# Dual_Servo_Module.net
KiCad netlist of a schematic drawn in EAGLE
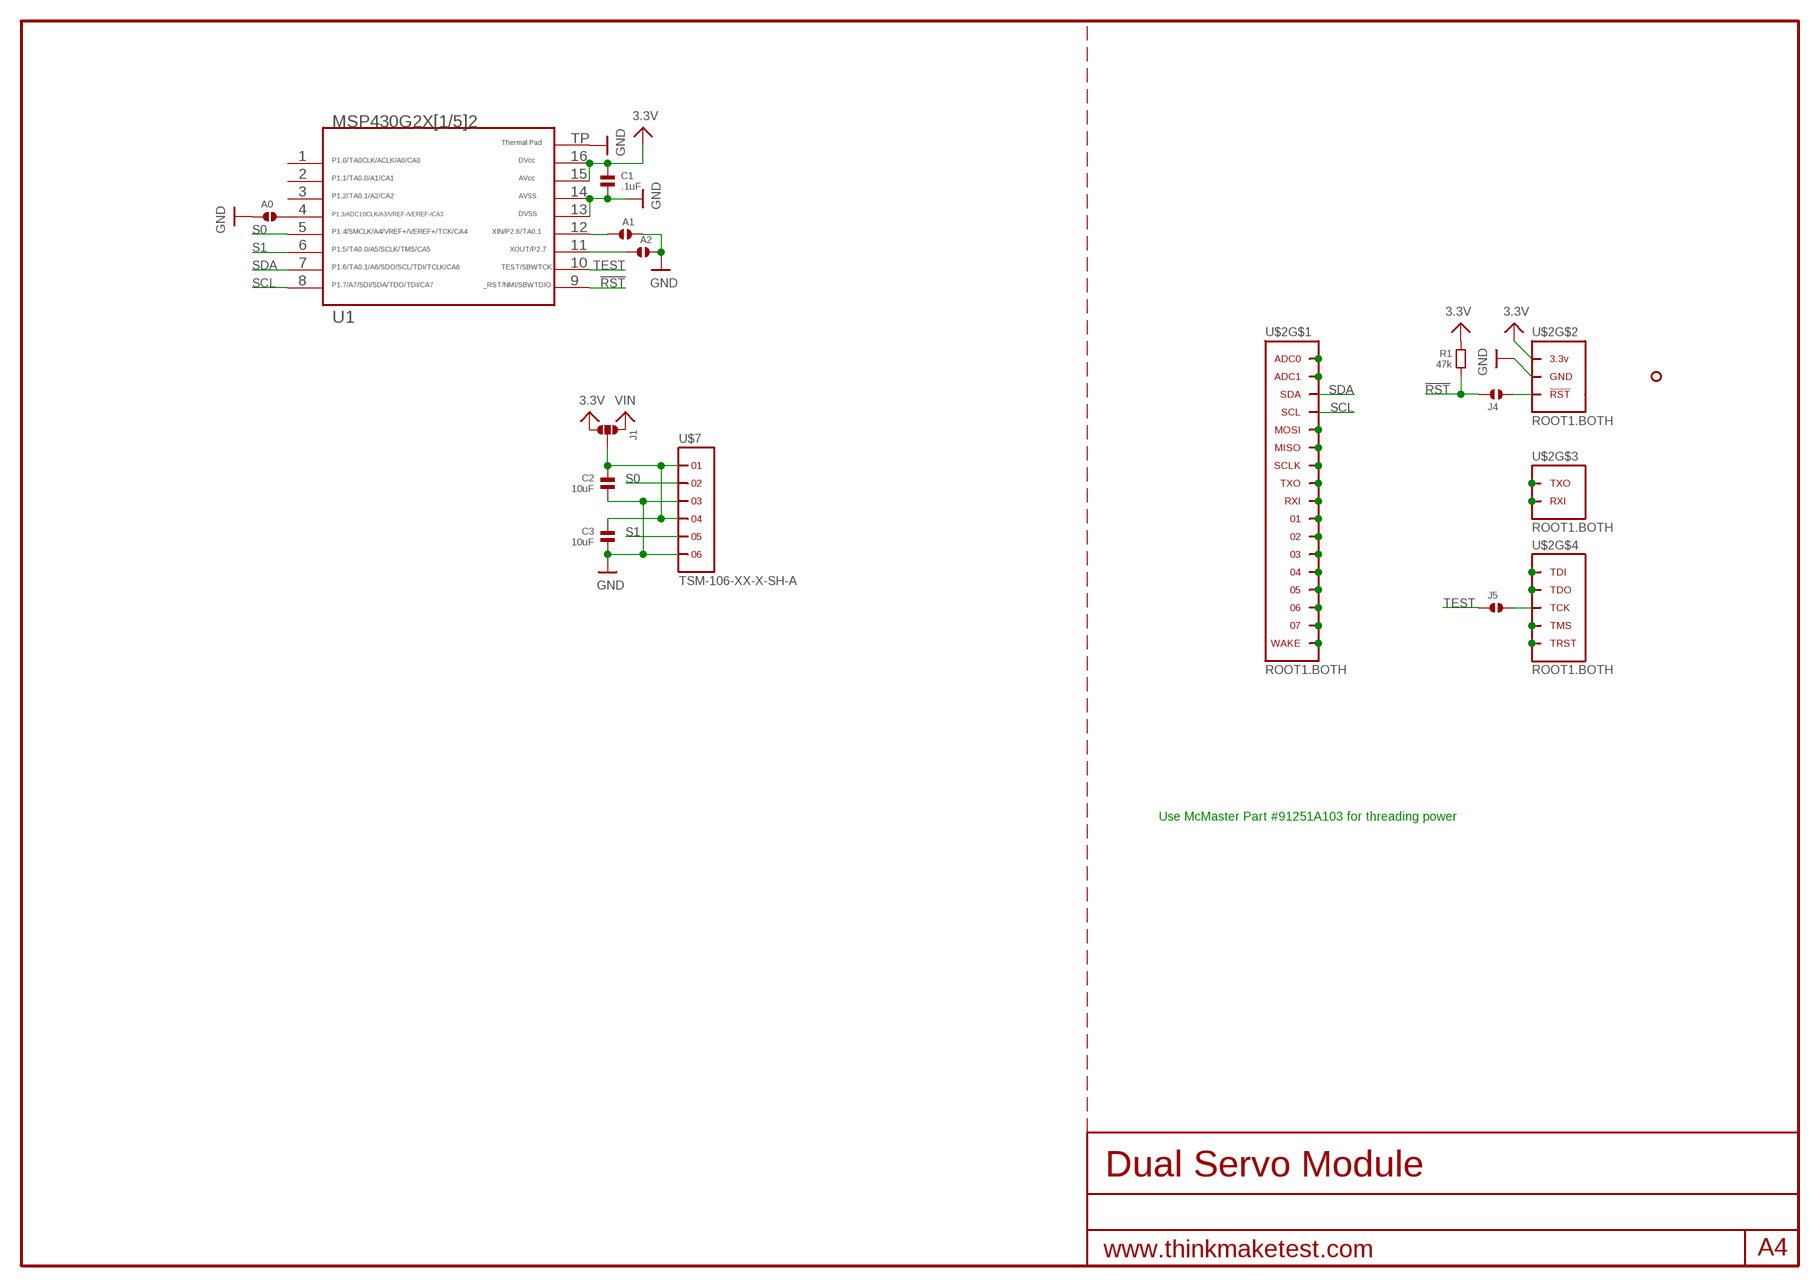
[diagram p0: schematic, sheet 1]

(export (version "E")
  (design (tool "Eeschema 10.0.6"))
  (components
    (comp (ref "A0")
      (value "SOLDERJUMPER.2.MED")
      (footprint "eagle-import:2.MED")
      (libsource (lib "eagle-import") (part "SOLDERJUMPER.2.MED"))
    )
    (comp (ref "A1")
      (value "SOLDERJUMPER.2.MED")
      (footprint "eagle-import:2.MED")
      (libsource (lib "eagle-import") (part "SOLDERJUMPER.2.MED"))
    )
    (comp (ref "A2")
      (value "SOLDERJUMPER.2.MED")
      (footprint "eagle-import:2.MED")
      (libsource (lib "eagle-import") (part "SOLDERJUMPER.2.MED"))
    )
    (comp (ref "C1")
      (value ".1uF")
      (footprint "eagle-import:0603")
      (libsource (lib "eagle-import") (part "CAPACITOR.0603"))
    )
    (comp (ref "C2")
      (value "10uF")
      (footprint "eagle-import:0805")
      (libsource (lib "eagle-import") (part "CAPACITOR.0805"))
    )
    (comp (ref "C3")
      (value "10uF")
      (footprint "eagle-import:0805")
      (libsource (lib "eagle-import") (part "CAPACITOR.0805"))
    )
    (comp (ref "J1")
      (value "SOLDERJUMPER.3.LRG.12")
      (footprint "eagle-import:3.LRG.12")
      (libsource (lib "eagle-import") (part "SOLDERJUMPER.3.LRG.12"))
    )
    (comp (ref "J4")
      (value "SOLDERJUMPER.2.MED")
      (footprint "eagle-import:2.MED")
      (libsource (lib "eagle-import") (part "SOLDERJUMPER.2.MED"))
    )
    (comp (ref "J5")
      (value "SOLDERJUMPER.2.MED")
      (footprint "eagle-import:2.MED")
      (libsource (lib "eagle-import") (part "SOLDERJUMPER.2.MED"))
    )
    (comp (ref "R1")
      (value "47k")
      (footprint "eagle-import:0603")
      (libsource (lib "eagle-import") (part "RESISTOR.0603"))
    )
    (comp (ref "U$2")
      (value "ROOT1.BOTH")
      (footprint "eagle-import:ROOT1.BOTH")
      (libsource (lib "eagle-import") (part "ROOT1.BOTH"))
    )
    (comp (ref "U$4")
      (value "HOLE.#2")
      (footprint "eagle-import:#2")
      (libsource (lib "eagle-import") (part "HOLE.#2"))
    )
    (comp (ref "U$7")
      (value "TSM-106-XX-X-SH-A")
      (footprint "eagle-import:TSM-106-XX-X-SH-A")
      (libsource (lib "eagle-import") (part "TSM-106-XX-X-SH-A"))
    )
    (comp (ref "U1")
      (value "MSP430G2452.QFN16")
      (footprint "eagle-import:RSA16")
      (libsource (lib "eagle-import") (part "G2X[1/5]2---RSA16"))
    )
  )
  (nets
    (net (code "1") (name "/S0") (class "Default")
      (node (ref "U$7") (pin "2") (pinfunction "2_2") (pintype "bidirectional"))
      (node (ref "U1") (pin "5") (pinfunction "5_5") (pintype "bidirectional"))
    )
    (net (code "2") (name "/S1") (class "Default")
      (node (ref "U$7") (pin "5") (pinfunction "5_5") (pintype "bidirectional"))
      (node (ref "U1") (pin "6") (pinfunction "6_6") (pintype "bidirectional"))
    )
    (net (code "3") (name "/SCL") (class "Default")
      (node (ref "U$2") (pin "SCL") (pinfunction "SCL_SCL") (pintype "bidirectional"))
      (node (ref "U$2") (pin "SCL@1") (pinfunction "SCL_SCL@1") (pintype "bidirectional"))
      (node (ref "U$2") (pin "SCL@VIA") (pinfunction "SCL_SCL@VIA") (pintype "bidirectional"))
      (node (ref "U1") (pin "8") (pinfunction "8_8") (pintype "bidirectional"))
    )
    (net (code "4") (name "/SDA") (class "Default")
      (node (ref "U$2") (pin "SDA") (pinfunction "SDA_SDA") (pintype "bidirectional"))
      (node (ref "U$2") (pin "SDA@1") (pinfunction "SDA_SDA@1") (pintype "bidirectional"))
      (node (ref "U$2") (pin "SDA@VIA") (pinfunction "SDA_SDA@VIA") (pintype "bidirectional"))
      (node (ref "U1") (pin "7") (pinfunction "7_7") (pintype "bidirectional"))
    )
    (net (code "5") (name "/TEST") (class "Default")
      (node (ref "J5") (pin "1") (pinfunction "1_1") (pintype "bidirectional"))
      (node (ref "U1") (pin "10") (pinfunction "10_10") (pintype "bidirectional"))
    )
    (net (code "6") (name "/~{RST}") (class "Default")
      (node (ref "J4") (pin "1") (pinfunction "1_1") (pintype "bidirectional"))
      (node (ref "R1") (pin "2") (pinfunction "2_2") (pintype "bidirectional"))
      (node (ref "U1") (pin "9") (pinfunction "9_9") (pintype "bidirectional"))
    )
    (net (code "7") (name "3.3V") (class "Default")
      (node (ref "C1") (pin "1") (pinfunction "1_1") (pintype "bidirectional"))
      (node (ref "J1") (pin "3") (pinfunction "3_3") (pintype "bidirectional"))
      (node (ref "R1") (pin "1") (pinfunction "1_1") (pintype "bidirectional"))
      (node (ref "U$2") (pin "3.3V@1") (pinfunction "3.3V_3.3V@1") (pintype "bidirectional"))
      (node (ref "U$2") (pin "3.3V@10") (pinfunction "3.3V_3.3V@10") (pintype "bidirectional"))
      (node (ref "U$2") (pin "3.3V@11") (pinfunction "3.3V_3.3V@11") (pintype "bidirectional"))
      (node (ref "U$2") (pin "3.3V@12") (pinfunction "3.3V_3.3V@12") (pintype "bidirectional"))
      (node (ref "U$2") (pin "3.3V@13") (pinfunction "3.3V_3.3V@13") (pintype "bidirectional"))
      (node (ref "U$2") (pin "3.3V@14") (pinfunction "3.3V_3.3V@14") (pintype "bidirectional"))
      (node (ref "U$2") (pin "3.3V@15") (pinfunction "3.3V_3.3V@15") (pintype "bidirectional"))
      (node (ref "U$2") (pin "3.3V@16") (pinfunction "3.3V_3.3V@16") (pintype "bidirectional"))
      (node (ref "U$2") (pin "3.3V@17") (pinfunction "3.3V_3.3V@17") (pintype "bidirectional"))
      (node (ref "U$2") (pin "3.3V@18") (pinfunction "3.3V_3.3V@18") (pintype "bidirectional"))
      (node (ref "U$2") (pin "3.3V@19") (pinfunction "3.3V_3.3V@19") (pintype "bidirectional"))
      (node (ref "U$2") (pin "3.3V@2") (pinfunction "3.3V_3.3V@2") (pintype "bidirectional"))
      (node (ref "U$2") (pin "3.3V@20") (pinfunction "3.3V_3.3V@20") (pintype "bidirectional"))
      (node (ref "U$2") (pin "3.3V@21") (pinfunction "3.3V_3.3V@21") (pintype "bidirectional"))
      (node (ref "U$2") (pin "3.3V@22") (pinfunction "3.3V_3.3V@22") (pintype "bidirectional"))
      (node (ref "U$2") (pin "3.3V@23") (pinfunction "3.3V_3.3V@23") (pintype "bidirectional"))
      (node (ref "U$2") (pin "3.3V@24") (pinfunction "3.3V_3.3V@24") (pintype "bidirectional"))
      (node (ref "U$2") (pin "3.3V@3") (pinfunction "3.3V_3.3V@3") (pintype "bidirectional"))
      (node (ref "U$2") (pin "3.3V@4") (pinfunction "3.3V_3.3V@4") (pintype "bidirectional"))
      (node (ref "U$2") (pin "3.3V@5") (pinfunction "3.3V_3.3V@5") (pintype "bidirectional"))
      (node (ref "U$2") (pin "3.3V@6") (pinfunction "3.3V_3.3V@6") (pintype "bidirectional"))
      (node (ref "U$2") (pin "3.3V@7") (pinfunction "3.3V_3.3V@7") (pintype "bidirectional"))
      (node (ref "U$2") (pin "3.3V@8") (pinfunction "3.3V_3.3V@8") (pintype "bidirectional"))
      (node (ref "U$2") (pin "3.3V@9") (pinfunction "3.3V_3.3V@9") (pintype "bidirectional"))
      (node (ref "U$2") (pin "3.3V@VIA") (pinfunction "3.3V_3.3V@VIA") (pintype "bidirectional"))
      (node (ref "U1") (pin "15") (pinfunction "15_15") (pintype "bidirectional"))
      (node (ref "U1") (pin "16") (pinfunction "16_16") (pintype "bidirectional"))
    )
    (net (code "8") (name "GND") (class "Default")
      (node (ref "A0") (pin "1") (pinfunction "1_1") (pintype "bidirectional"))
      (node (ref "A1") (pin "1") (pinfunction "1_1") (pintype "bidirectional"))
      (node (ref "A2") (pin "1") (pinfunction "1_1") (pintype "bidirectional"))
      (node (ref "C1") (pin "2") (pinfunction "2_2") (pintype "bidirectional"))
      (node (ref "C2") (pin "2") (pinfunction "2_2") (pintype "bidirectional"))
      (node (ref "C3") (pin "2") (pinfunction "2_2") (pintype "bidirectional"))
      (node (ref "U$2") (pin "GND@1") (pinfunction "GND_GND@1") (pintype "bidirectional"))
      (node (ref "U$2") (pin "GND@10") (pinfunction "GND_GND@10") (pintype "bidirectional"))
      (node (ref "U$2") (pin "GND@11") (pinfunction "GND_GND@11") (pintype "bidirectional"))
      (node (ref "U$2") (pin "GND@12") (pinfunction "GND_GND@12") (pintype "bidirectional"))
      (node (ref "U$2") (pin "GND@13") (pinfunction "GND_GND@13") (pintype "bidirectional"))
      (node (ref "U$2") (pin "GND@14") (pinfunction "GND_GND@14") (pintype "bidirectional"))
      (node (ref "U$2") (pin "GND@15") (pinfunction "GND_GND@15") (pintype "bidirectional"))
      (node (ref "U$2") (pin "GND@16") (pinfunction "GND_GND@16") (pintype "bidirectional"))
      (node (ref "U$2") (pin "GND@17") (pinfunction "GND_GND@17") (pintype "bidirectional"))
      (node (ref "U$2") (pin "GND@18") (pinfunction "GND_GND@18") (pintype "bidirectional"))
      (node (ref "U$2") (pin "GND@19") (pinfunction "GND_GND@19") (pintype "bidirectional"))
      (node (ref "U$2") (pin "GND@2") (pinfunction "GND_GND@2") (pintype "bidirectional"))
      (node (ref "U$2") (pin "GND@20") (pinfunction "GND_GND@20") (pintype "bidirectional"))
      (node (ref "U$2") (pin "GND@21") (pinfunction "GND_GND@21") (pintype "bidirectional"))
      (node (ref "U$2") (pin "GND@22") (pinfunction "GND_GND@22") (pintype "bidirectional"))
      (node (ref "U$2") (pin "GND@23") (pinfunction "GND_GND@23") (pintype "bidirectional"))
      (node (ref "U$2") (pin "GND@24") (pinfunction "GND_GND@24") (pintype "bidirectional"))
      (node (ref "U$2") (pin "GND@25") (pinfunction "GND_GND@25") (pintype "bidirectional"))
      (node (ref "U$2") (pin "GND@26") (pinfunction "GND_GND@26") (pintype "bidirectional"))
      (node (ref "U$2") (pin "GND@3") (pinfunction "GND_GND@3") (pintype "bidirectional"))
      (node (ref "U$2") (pin "GND@4") (pinfunction "GND_GND@4") (pintype "bidirectional"))
      (node (ref "U$2") (pin "GND@5") (pinfunction "GND_GND@5") (pintype "bidirectional"))
      (node (ref "U$2") (pin "GND@6") (pinfunction "GND_GND@6") (pintype "bidirectional"))
      (node (ref "U$2") (pin "GND@7") (pinfunction "GND_GND@7") (pintype "bidirectional"))
      (node (ref "U$2") (pin "GND@8") (pinfunction "GND_GND@8") (pintype "bidirectional"))
      (node (ref "U$2") (pin "GND@9") (pinfunction "GND_GND@9") (pintype "bidirectional"))
      (node (ref "U$2") (pin "GND@VIA") (pinfunction "GND_GND@VIA") (pintype "bidirectional"))
      (node (ref "U$7") (pin "3") (pinfunction "3_3") (pintype "bidirectional"))
      (node (ref "U$7") (pin "6") (pinfunction "6_6") (pintype "bidirectional"))
      (node (ref "U1") (pin "13") (pinfunction "13_13") (pintype "bidirectional"))
      (node (ref "U1") (pin "14") (pinfunction "14_14") (pintype "bidirectional"))
      (node (ref "U1") (pin "TP") (pinfunction "TP_TP") (pintype "bidirectional"))
    )
    (net (code "9") (name "Net-(A0-Pad2)") (class "Default")
      (node (ref "A0") (pin "2") (pinfunction "2_2") (pintype "bidirectional"))
      (node (ref "U1") (pin "4") (pinfunction "4_4") (pintype "bidirectional"))
    )
    (net (code "10") (name "Net-(A1-Pad2)") (class "Default")
      (node (ref "A1") (pin "2") (pinfunction "2_2") (pintype "bidirectional"))
      (node (ref "U1") (pin "12") (pinfunction "12_12") (pintype "bidirectional"))
    )
    (net (code "11") (name "Net-(A2-Pad2)") (class "Default")
      (node (ref "A2") (pin "2") (pinfunction "2_2") (pintype "bidirectional"))
      (node (ref "U1") (pin "11") (pinfunction "11_11") (pintype "bidirectional"))
    )
    (net (code "12") (name "Net-(C2-Pad1)") (class "Default")
      (node (ref "C2") (pin "1") (pinfunction "1_1") (pintype "bidirectional"))
      (node (ref "C3") (pin "1") (pinfunction "1_1") (pintype "bidirectional"))
      (node (ref "J1") (pin "2") (pinfunction "2_2") (pintype "bidirectional"))
      (node (ref "U$7") (pin "1") (pinfunction "1_1") (pintype "bidirectional"))
      (node (ref "U$7") (pin "4") (pinfunction "4_4") (pintype "bidirectional"))
    )
    (net (code "13") (name "Net-(J4-Pad2)") (class "Default")
      (node (ref "J4") (pin "2") (pinfunction "2_2") (pintype "bidirectional"))
      (node (ref "U$2") (pin "RST") (pinfunction "~{RST}_RST") (pintype "bidirectional"))
      (node (ref "U$2") (pin "RST@1") (pinfunction "~{RST}_RST@1") (pintype "bidirectional"))
      (node (ref "U$2") (pin "RST@VIA") (pinfunction "~{RST}_RST@VIA") (pintype "bidirectional"))
    )
    (net (code "14") (name "Net-(J5-Pad2)") (class "Default")
      (node (ref "J5") (pin "2") (pinfunction "2_2") (pintype "bidirectional"))
      (node (ref "U$2") (pin "TCK") (pinfunction "TCK_TCK") (pintype "bidirectional"))
      (node (ref "U$2") (pin "TCK@1") (pinfunction "TCK_TCK@1") (pintype "bidirectional"))
      (node (ref "U$2") (pin "TCK@VIA") (pinfunction "TCK_TCK@VIA") (pintype "bidirectional"))
    )
    (net (code "15") (name "Net-(U$2-Pad01)") (class "Default")
      (node (ref "U$2") (pin "01") (pinfunction "01_01") (pintype "bidirectional"))
      (node (ref "U$2") (pin "01@1") (pinfunction "01_01@1") (pintype "bidirectional"))
      (node (ref "U$2") (pin "01@VIA") (pinfunction "01_01@VIA") (pintype "bidirectional"))
    )
    (net (code "16") (name "Net-(U$2-Pad02)") (class "Default")
      (node (ref "U$2") (pin "02") (pinfunction "02_02") (pintype "bidirectional"))
      (node (ref "U$2") (pin "02@1") (pinfunction "02_02@1") (pintype "bidirectional"))
      (node (ref "U$2") (pin "02@VIA") (pinfunction "02_02@VIA") (pintype "bidirectional"))
    )
    (net (code "17") (name "Net-(U$2-Pad03)") (class "Default")
      (node (ref "U$2") (pin "03") (pinfunction "03_03") (pintype "bidirectional"))
      (node (ref "U$2") (pin "03@1") (pinfunction "03_03@1") (pintype "bidirectional"))
      (node (ref "U$2") (pin "03@VIA") (pinfunction "03_03@VIA") (pintype "bidirectional"))
    )
    (net (code "18") (name "Net-(U$2-Pad04)") (class "Default")
      (node (ref "U$2") (pin "04") (pinfunction "04_04") (pintype "bidirectional"))
      (node (ref "U$2") (pin "04@1") (pinfunction "04_04@1") (pintype "bidirectional"))
      (node (ref "U$2") (pin "04@VIA") (pinfunction "04_04@VIA") (pintype "bidirectional"))
    )
    (net (code "19") (name "Net-(U$2-Pad05)") (class "Default")
      (node (ref "U$2") (pin "05") (pinfunction "05_05") (pintype "bidirectional"))
      (node (ref "U$2") (pin "05@1") (pinfunction "05_05@1") (pintype "bidirectional"))
      (node (ref "U$2") (pin "05@VIA") (pinfunction "05_05@VIA") (pintype "bidirectional"))
    )
    (net (code "20") (name "Net-(U$2-Pad06)") (class "Default")
      (node (ref "U$2") (pin "06") (pinfunction "06_06") (pintype "bidirectional"))
      (node (ref "U$2") (pin "06@1") (pinfunction "06_06@1") (pintype "bidirectional"))
      (node (ref "U$2") (pin "06@VIA") (pinfunction "06_06@VIA") (pintype "bidirectional"))
    )
    (net (code "21") (name "Net-(U$2-Pad07)") (class "Default")
      (node (ref "U$2") (pin "07") (pinfunction "07_07") (pintype "bidirectional"))
      (node (ref "U$2") (pin "07@1") (pinfunction "07_07@1") (pintype "bidirectional"))
      (node (ref "U$2") (pin "07@VIA") (pinfunction "07_07@VIA") (pintype "bidirectional"))
    )
    (net (code "22") (name "Net-(U$2-PadADC0)") (class "Default")
      (node (ref "U$2") (pin "ADC0") (pinfunction "ADC0_ADC0") (pintype "bidirectional"))
      (node (ref "U$2") (pin "ADC0@1") (pinfunction "ADC0_ADC0@1") (pintype "bidirectional"))
      (node (ref "U$2") (pin "ADC0@VIA") (pinfunction "ADC0_ADC0@VIA") (pintype "bidirectional"))
    )
    (net (code "23") (name "Net-(U$2-PadADC1)") (class "Default")
      (node (ref "U$2") (pin "ADC1") (pinfunction "ADC1_ADC1") (pintype "bidirectional"))
      (node (ref "U$2") (pin "ADC1@1") (pinfunction "ADC1_ADC1@1") (pintype "bidirectional"))
      (node (ref "U$2") (pin "ADC1@VIA") (pinfunction "ADC1_ADC1@VIA") (pintype "bidirectional"))
    )
    (net (code "24") (name "Net-(U$2-PadMISO)") (class "Default")
      (node (ref "U$2") (pin "MISO") (pinfunction "MISO_MISO") (pintype "bidirectional"))
      (node (ref "U$2") (pin "MISO@1") (pinfunction "MISO_MISO@1") (pintype "bidirectional"))
      (node (ref "U$2") (pin "MISO@VIA") (pinfunction "MISO_MISO@VIA") (pintype "bidirectional"))
    )
    (net (code "25") (name "Net-(U$2-PadMOSI)") (class "Default")
      (node (ref "U$2") (pin "MOSI") (pinfunction "MOSI_MOSI") (pintype "bidirectional"))
      (node (ref "U$2") (pin "MOSI@1") (pinfunction "MOSI_MOSI@1") (pintype "bidirectional"))
      (node (ref "U$2") (pin "MOSI@VIA") (pinfunction "MOSI_MOSI@VIA") (pintype "bidirectional"))
    )
    (net (code "26") (name "Net-(U$2-PadRXI)") (class "Default")
      (node (ref "U$2") (pin "RXI") (pinfunction "RXI_RXI") (pintype "bidirectional"))
      (node (ref "U$2") (pin "RXI@1") (pinfunction "RXI_RXI@1") (pintype "bidirectional"))
      (node (ref "U$2") (pin "RXI@VIA") (pinfunction "RXI_RXI@VIA") (pintype "bidirectional"))
    )
    (net (code "27") (name "Net-(U$2-PadSCLK)") (class "Default")
      (node (ref "U$2") (pin "SCLK") (pinfunction "SCLK_SCLK") (pintype "bidirectional"))
      (node (ref "U$2") (pin "SCLK@1") (pinfunction "SCLK_SCLK@1") (pintype "bidirectional"))
      (node (ref "U$2") (pin "SCLK@VIA") (pinfunction "SCLK_SCLK@VIA") (pintype "bidirectional"))
    )
    (net (code "28") (name "Net-(U$2-PadTDI)") (class "Default")
      (node (ref "U$2") (pin "TDI") (pinfunction "TDI_TDI") (pintype "bidirectional"))
      (node (ref "U$2") (pin "TDI@1") (pinfunction "TDI_TDI@1") (pintype "bidirectional"))
      (node (ref "U$2") (pin "TDI@VIA") (pinfunction "TDI_TDI@VIA") (pintype "bidirectional"))
    )
    (net (code "29") (name "Net-(U$2-PadTDO)") (class "Default")
      (node (ref "U$2") (pin "TDO") (pinfunction "TDO_TDO") (pintype "bidirectional"))
      (node (ref "U$2") (pin "TDO@1") (pinfunction "TDO_TDO@1") (pintype "bidirectional"))
      (node (ref "U$2") (pin "TDO@VIA") (pinfunction "TDO_TDO@VIA") (pintype "bidirectional"))
    )
    (net (code "30") (name "Net-(U$2-PadTMS)") (class "Default")
      (node (ref "U$2") (pin "TMS") (pinfunction "TMS_TMS") (pintype "bidirectional"))
      (node (ref "U$2") (pin "TMS@1") (pinfunction "TMS_TMS@1") (pintype "bidirectional"))
      (node (ref "U$2") (pin "TMS@VIA") (pinfunction "TMS_TMS@VIA") (pintype "bidirectional"))
    )
    (net (code "31") (name "Net-(U$2-PadTRST)") (class "Default")
      (node (ref "U$2") (pin "TRST") (pinfunction "TRST_TRST") (pintype "bidirectional"))
      (node (ref "U$2") (pin "TRST@1") (pinfunction "TRST_TRST@1") (pintype "bidirectional"))
      (node (ref "U$2") (pin "TRST@VIA") (pinfunction "TRST_TRST@VIA") (pintype "bidirectional"))
    )
    (net (code "32") (name "Net-(U$2-PadTXO)") (class "Default")
      (node (ref "U$2") (pin "TXO") (pinfunction "TXO_TXO") (pintype "bidirectional"))
      (node (ref "U$2") (pin "TXO@1") (pinfunction "TXO_TXO@1") (pintype "bidirectional"))
      (node (ref "U$2") (pin "TXO@VIA") (pinfunction "TXO_TXO@VIA") (pintype "bidirectional"))
    )
    (net (code "33") (name "Net-(U$2-PadWAKE)") (class "Default")
      (node (ref "U$2") (pin "WAKE") (pinfunction "WAKE_WAKE") (pintype "bidirectional"))
      (node (ref "U$2") (pin "WAKE@1") (pinfunction "WAKE_WAKE@1") (pintype "bidirectional"))
      (node (ref "U$2") (pin "WAKE@VIA") (pinfunction "WAKE_WAKE@VIA") (pintype "bidirectional"))
    )
    (net (code "34") (name "Net-(U$2C-RXI-PadRXI.DBG)") (class "Default")
      (node (ref "U$2") (pin "RXI.DBG") (pinfunction "RXI_RXI.DBG") (pintype "bidirectional"))
      (node (ref "U$2") (pin "RXI.DBG@1") (pinfunction "RXI_RXI.DBG@1") (pintype "bidirectional"))
      (node (ref "U$2") (pin "RXI.DBG@VIA") (pinfunction "RXI_RXI.DBG@VIA") (pintype "bidirectional"))
    )
    (net (code "35") (name "Net-(U$2C-TXO-PadTXO.DBG)") (class "Default")
      (node (ref "U$2") (pin "TXO.DBG") (pinfunction "TXO_TXO.DBG") (pintype "bidirectional"))
      (node (ref "U$2") (pin "TXO.DBG@1") (pinfunction "TXO_TXO.DBG@1") (pintype "bidirectional"))
      (node (ref "U$2") (pin "TXO.DBG@VIA") (pinfunction "TXO_TXO.DBG@VIA") (pintype "bidirectional"))
    )
    (net (code "36") (name "VIN") (class "Default")
      (node (ref "J1") (pin "1") (pinfunction "1_1") (pintype "bidirectional"))
    )
    (net (code "37") (name "unconnected-(U1-Pad1)") (class "Default")
      (node (ref "U1") (pin "1") (pinfunction "1_1") (pintype "bidirectional"))
    )
    (net (code "38") (name "unconnected-(U1-Pad2)") (class "Default")
      (node (ref "U1") (pin "2") (pinfunction "2_2") (pintype "bidirectional"))
    )
    (net (code "39") (name "unconnected-(U1-Pad3)") (class "Default")
      (node (ref "U1") (pin "3") (pinfunction "3_3") (pintype "bidirectional"))
    )
  )
)
